# Power.net
KiCad netlist of a schematic drawn in Altium Designer
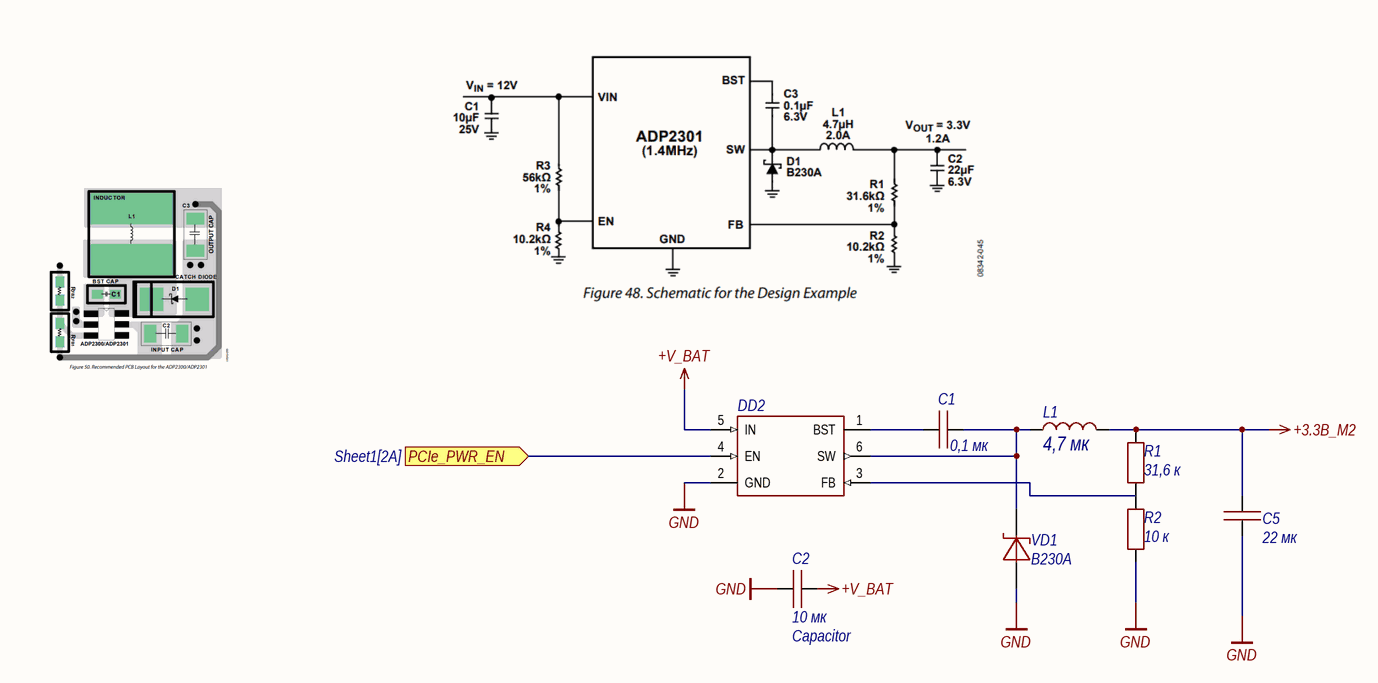
[diagram p0: Power.SchDoc]

(export (version "E")
  (design (tool "Eeschema 10.0.6"))
  (components
    (comp (ref "C1")
      (value "0,1 мк")
      (footprint "0603C")
      (description "Конденсатор")
      (fields (field (name "PART NUMBER") "Capacitor_0,1u_10_50V_X7R_0603C") (field (name "TOLERANCE") "0,1"))
      (libsource (lib "Hydrolib") (part "Capacitor"))
    )
    (comp (ref "C2")
      (value "Capacitor")
      (footprint "1210C")
      (description "Конденсатор")
      (fields
        (field (name "ALTIUM_VALUE") "10 мк")
        (field (name "PART NUMBER") "Capacitor_10u_10_35V_X7R_1210C")
        (field (name "TOLERANCE") "0,1")
      )
      (libsource (lib "Hydrolib") (part "Capacitor"))
    )
    (comp (ref "C5")
      (value "22 мк")
      (footprint "1210C")
      (description "Конденсатор")
      (fields (field (name "PART NUMBER") "Capacitor_22u_10_25V_X7R_1210C") (field (name "TOLERANCE") "0,1"))
      (libsource (lib "Hydrolib") (part "Capacitor"))
    )
    (comp (ref "DD2")
      (value "Повышающий DC-DC преобразователь 2А 1.2МГц")
      (libsource (lib "Hydrolib") (part "ADP2300"))
    )
    (comp (ref "L1")
      (value "4,7 мк")
      (footprint "IHLP-2525")
      (description "ЧИП-индуктивность экранированная 4,7мкГн ±20% 5,5A 40мОм 2525")
      (fields (field (name "PART NUMBER") "IHLP2525CZER4R7M01"))
      (libsource (lib "Hydrolib") (part "Inductance"))
    )
    (comp (ref "R1")
      (value "31,6 к")
      (footprint "0603R")
      (description "Резистор номиналом 31,6 кОм и точностью 1%")
      (fields (field (name "PART NUMBER") "Resistor_31.6k_1_0603") (field (name "TOLERANCE") "1%"))
      (libsource (lib "Hydrolib") (part "Resistor"))
    )
    (comp (ref "R2")
      (value "10 к")
      (footprint "0603R")
      (description "Резистор номиналом 10 кОм и точностью 1%")
      (fields (field (name "PART NUMBER") "Resistor_10k_1_0603") (field (name "TOLERANCE") "1%"))
      (libsource (lib "") (part "Resistor_1"))
    )
    (comp (ref "VD1")
      (value "B230A")
      (footprint "SMA")
      (description "Диод шоттки на 40 В, ном. ток 2.1 А")
      (fields (field (name "PART NUMBER") "15MQ040N"))
      (libsource (lib "Hydrolib") (part "Schottky_diode"))
    )
  )
  (nets
    (net (code "1") (name "+3.3В_M2") (class "Default")
      (node (ref "C5") (pin "2") (pinfunction "2_2") (pintype "passive"))
      (node (ref "L1") (pin "2") (pinfunction "2_2") (pintype "passive"))
      (node (ref "R1") (pin "1") (pinfunction "1_1") (pintype "passive"))
    )
    (net (code "2") (name "+V_BAT") (class "Default")
      (node (ref "C2") (pin "2") (pinfunction "2_2") (pintype "passive"))
      (node (ref "DD2") (pin "5") (pinfunction "IN_5") (pintype "input"))
    )
    (net (code "3") (name "/PCIe_PWR_EN") (class "Default")
      (node (ref "DD2") (pin "4") (pinfunction "EN_4") (pintype "input"))
    )
    (net (code "4") (name "GND") (class "Default")
      (node (ref "C2") (pin "1") (pinfunction "1_1") (pintype "passive"))
      (node (ref "C5") (pin "1") (pinfunction "1_1") (pintype "passive"))
      (node (ref "DD2") (pin "2") (pinfunction "GND_2") (pintype "power_in"))
      (node (ref "R2") (pin "1") (pinfunction "1_1") (pintype "passive"))
      (node (ref "VD1") (pin "1") (pinfunction "1_1") (pintype "passive"))
    )
    (net (code "5") (name "Net-(DD2-BST)") (class "Default")
      (node (ref "C1") (pin "1") (pinfunction "1_1") (pintype "passive"))
      (node (ref "DD2") (pin "1") (pinfunction "BST_1") (pintype "power_in"))
    )
    (net (code "6") (name "Net-(DD2-FB)") (class "Default")
      (node (ref "DD2") (pin "3") (pinfunction "FB_3") (pintype "input"))
      (node (ref "R1") (pin "2") (pinfunction "2_2") (pintype "passive"))
      (node (ref "R2") (pin "2") (pinfunction "2_2") (pintype "passive"))
    )
    (net (code "7") (name "Net-(DD2-SW)") (class "Default")
      (node (ref "C1") (pin "2") (pinfunction "2_2") (pintype "passive"))
      (node (ref "DD2") (pin "6") (pinfunction "SW_6") (pintype "output"))
      (node (ref "L1") (pin "1") (pinfunction "1_1") (pintype "passive"))
      (node (ref "VD1") (pin "2") (pinfunction "2_2") (pintype "passive"))
    )
  )
)
